# RJ45_Connector_and_ESD_Diodes.net
KiCad netlist of a schematic drawn in Altium Designer
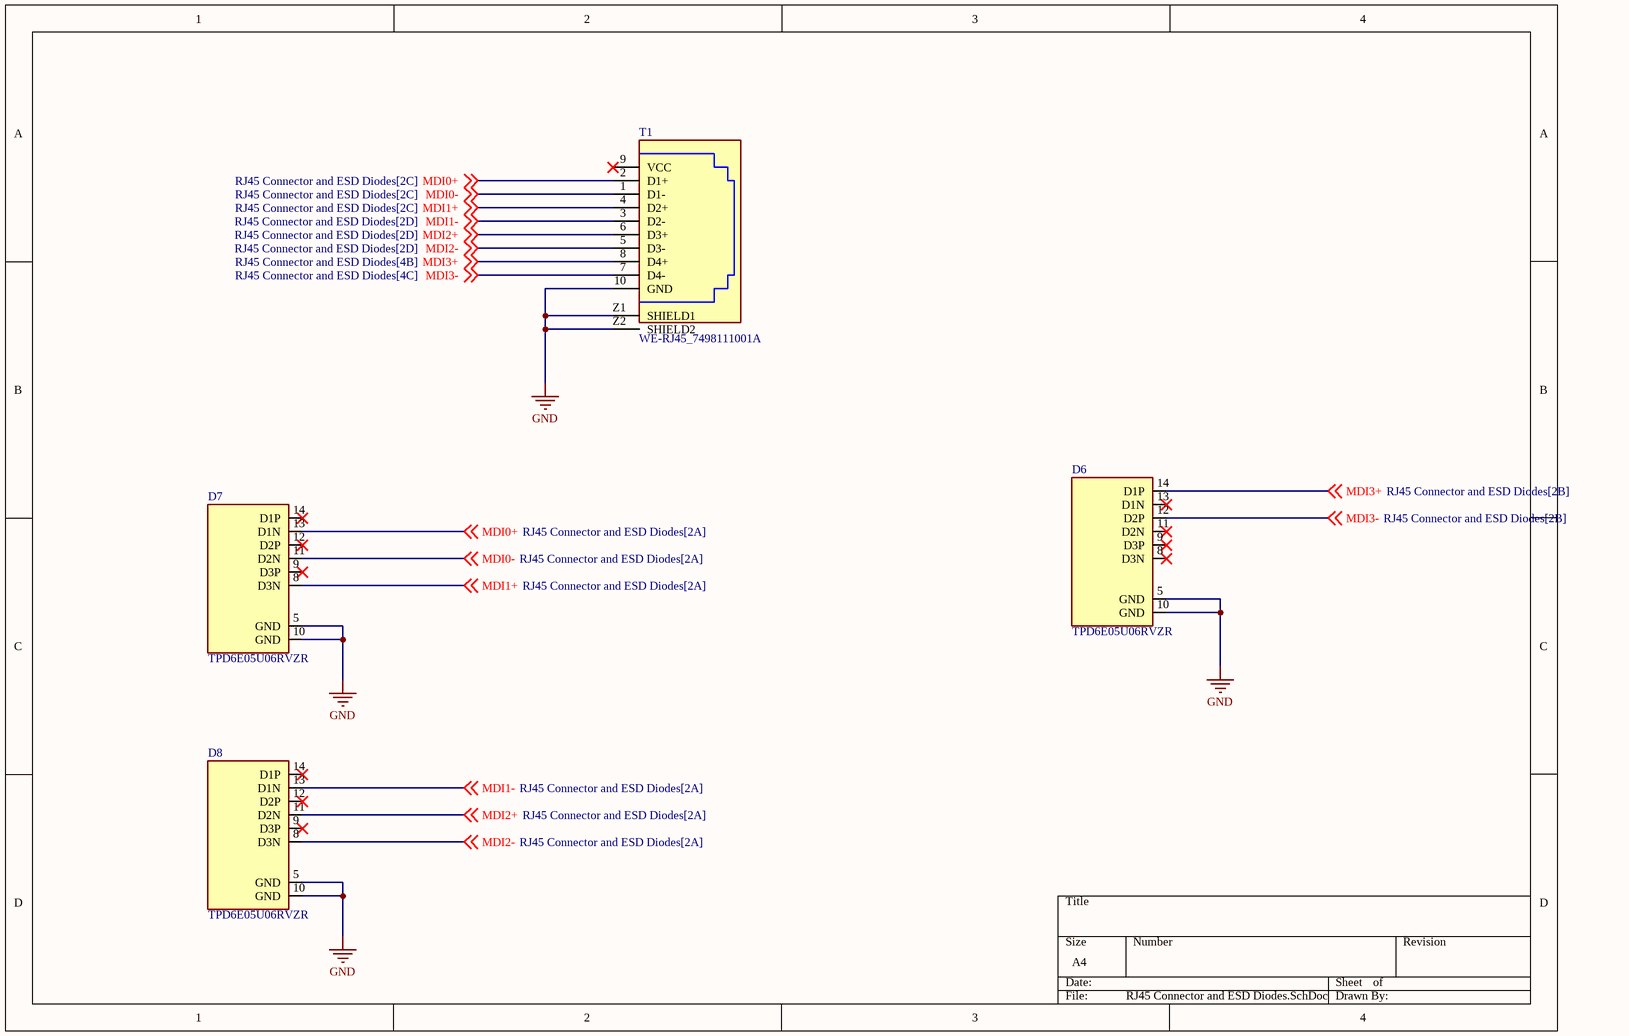
[diagram p0: RJ45 Connector and ESD Diodes.SchDoc]

(export (version "E")
  (design (tool "Eeschema 10.0.6"))
  (components
    (comp (ref "D6")
      (value "TPD6E05U06RVZR")
      (footprint "SON50P135X350X55-14N")
      (description "6-Channel Ultra low capacitance IEC ESD protection diodes 14-USON -40 to 125")
      (libsource (lib "TPD6E05U06RVZR") (part "TPD6E05U06RVZR"))
    )
    (comp (ref "D7")
      (value "TPD6E05U06RVZR")
      (footprint "SON50P135X350X55-14N")
      (description "6-Channel Ultra low capacitance IEC ESD protection diodes 14-USON -40 to 125")
      (libsource (lib "TPD6E05U06RVZR") (part "TPD6E05U06RVZR"))
    )
    (comp (ref "D8")
      (value "TPD6E05U06RVZR")
      (footprint "SON50P135X350X55-14N")
      (description "6-Channel Ultra low capacitance IEC ESD protection diodes 14-USON -40 to 125")
      (libsource (lib "TPD6E05U06RVZR") (part "TPD6E05U06RVZR"))
    )
    (comp (ref "T1")
      (value "WE-RJ45_7498111001A")
      (footprint "7498111001A")
      (description "EMI Gaskets, Sheets, Absorbers & Shielding Integrated RJ45 Transformer WE-RJ45LAN")
      (fields (field (name "MF") "WÃ¼rth Elektronik") (field (name "MP") "7498111001A"))
      (libsource (lib "WE-RJ45_7498111001A") (part "WE-RJ45_7498111001A"))
    )
  )
  (nets
    (net (code "1") (name "GND") (class "Default")
      (node (ref "D6") (pin "10") (pinfunction "GND_10") (pintype "power_in"))
      (node (ref "D6") (pin "5") (pinfunction "GND_5") (pintype "power_in"))
      (node (ref "D7") (pin "10") (pinfunction "GND_10") (pintype "power_in"))
      (node (ref "D7") (pin "5") (pinfunction "GND_5") (pintype "power_in"))
      (node (ref "D8") (pin "10") (pinfunction "GND_10") (pintype "power_in"))
      (node (ref "D8") (pin "5") (pinfunction "GND_5") (pintype "power_in"))
      (node (ref "T1") (pin "10") (pinfunction "GND_10") (pintype "passive"))
      (node (ref "T1") (pin "Z1") (pinfunction "SHIELD1_Z1") (pintype "passive"))
      (node (ref "T1") (pin "Z2") (pinfunction "SHIELD2_Z2") (pintype "passive"))
    )
    (net (code "2") (name "MDI0+") (class "Default")
      (node (ref "D7") (pin "13") (pinfunction "D1N_13") (pintype "bidirectional"))
      (node (ref "T1") (pin "2") (pinfunction "D1+_2") (pintype "passive"))
    )
    (net (code "3") (name "MDI0-") (class "Default")
      (node (ref "D7") (pin "11") (pinfunction "D2N_11") (pintype "bidirectional"))
      (node (ref "T1") (pin "1") (pinfunction "D1-_1") (pintype "passive"))
    )
    (net (code "4") (name "MDI1+") (class "Default")
      (node (ref "D7") (pin "8") (pinfunction "D3N_8") (pintype "bidirectional"))
      (node (ref "T1") (pin "4") (pinfunction "D2+_4") (pintype "passive"))
    )
    (net (code "5") (name "MDI1-") (class "Default")
      (node (ref "D8") (pin "13") (pinfunction "D1N_13") (pintype "bidirectional"))
      (node (ref "T1") (pin "3") (pinfunction "D2-_3") (pintype "passive"))
    )
    (net (code "6") (name "MDI2+") (class "Default")
      (node (ref "D8") (pin "11") (pinfunction "D2N_11") (pintype "bidirectional"))
      (node (ref "T1") (pin "6") (pinfunction "D3+_6") (pintype "passive"))
    )
    (net (code "7") (name "MDI2-") (class "Default")
      (node (ref "D8") (pin "8") (pinfunction "D3N_8") (pintype "bidirectional"))
      (node (ref "T1") (pin "5") (pinfunction "D3-_5") (pintype "passive"))
    )
    (net (code "8") (name "MDI3+") (class "Default")
      (node (ref "D6") (pin "14") (pinfunction "D1P_14") (pintype "bidirectional"))
      (node (ref "T1") (pin "8") (pinfunction "D4+_8") (pintype "passive"))
    )
    (net (code "9") (name "MDI3-") (class "Default")
      (node (ref "D6") (pin "12") (pinfunction "D2P_12") (pintype "bidirectional"))
      (node (ref "T1") (pin "7") (pinfunction "D4-_7") (pintype "passive"))
    )
    (net (code "10") (name "unconnected-(D6-D1N-Pad13)") (class "Default")
      (node (ref "D6") (pin "13") (pinfunction "D1N_13") (pintype "bidirectional+no_connect"))
    )
    (net (code "11") (name "unconnected-(D6-D2N-Pad11)") (class "Default")
      (node (ref "D6") (pin "11") (pinfunction "D2N_11") (pintype "bidirectional+no_connect"))
    )
    (net (code "12") (name "unconnected-(D6-D3N-Pad8)") (class "Default")
      (node (ref "D6") (pin "8") (pinfunction "D3N_8") (pintype "bidirectional+no_connect"))
    )
    (net (code "13") (name "unconnected-(D6-D3P-Pad9)") (class "Default")
      (node (ref "D6") (pin "9") (pinfunction "D3P_9") (pintype "bidirectional+no_connect"))
    )
    (net (code "14") (name "unconnected-(D7-D1P-Pad14)") (class "Default")
      (node (ref "D7") (pin "14") (pinfunction "D1P_14") (pintype "bidirectional+no_connect"))
    )
    (net (code "15") (name "unconnected-(D7-D2P-Pad12)") (class "Default")
      (node (ref "D7") (pin "12") (pinfunction "D2P_12") (pintype "bidirectional+no_connect"))
    )
    (net (code "16") (name "unconnected-(D7-D3P-Pad9)") (class "Default")
      (node (ref "D7") (pin "9") (pinfunction "D3P_9") (pintype "bidirectional+no_connect"))
    )
    (net (code "17") (name "unconnected-(D8-D1P-Pad14)") (class "Default")
      (node (ref "D8") (pin "14") (pinfunction "D1P_14") (pintype "bidirectional+no_connect"))
    )
    (net (code "18") (name "unconnected-(D8-D2P-Pad12)") (class "Default")
      (node (ref "D8") (pin "12") (pinfunction "D2P_12") (pintype "bidirectional+no_connect"))
    )
    (net (code "19") (name "unconnected-(D8-D3P-Pad9)") (class "Default")
      (node (ref "D8") (pin "9") (pinfunction "D3P_9") (pintype "bidirectional+no_connect"))
    )
    (net (code "20") (name "unconnected-(T1-VCC-Pad9)") (class "Default")
      (node (ref "T1") (pin "9") (pinfunction "VCC_9") (pintype "passive+no_connect"))
    )
  )
)
